# 02_-_CONNECTORS.net
KiCad netlist of a schematic drawn in Altium Designer
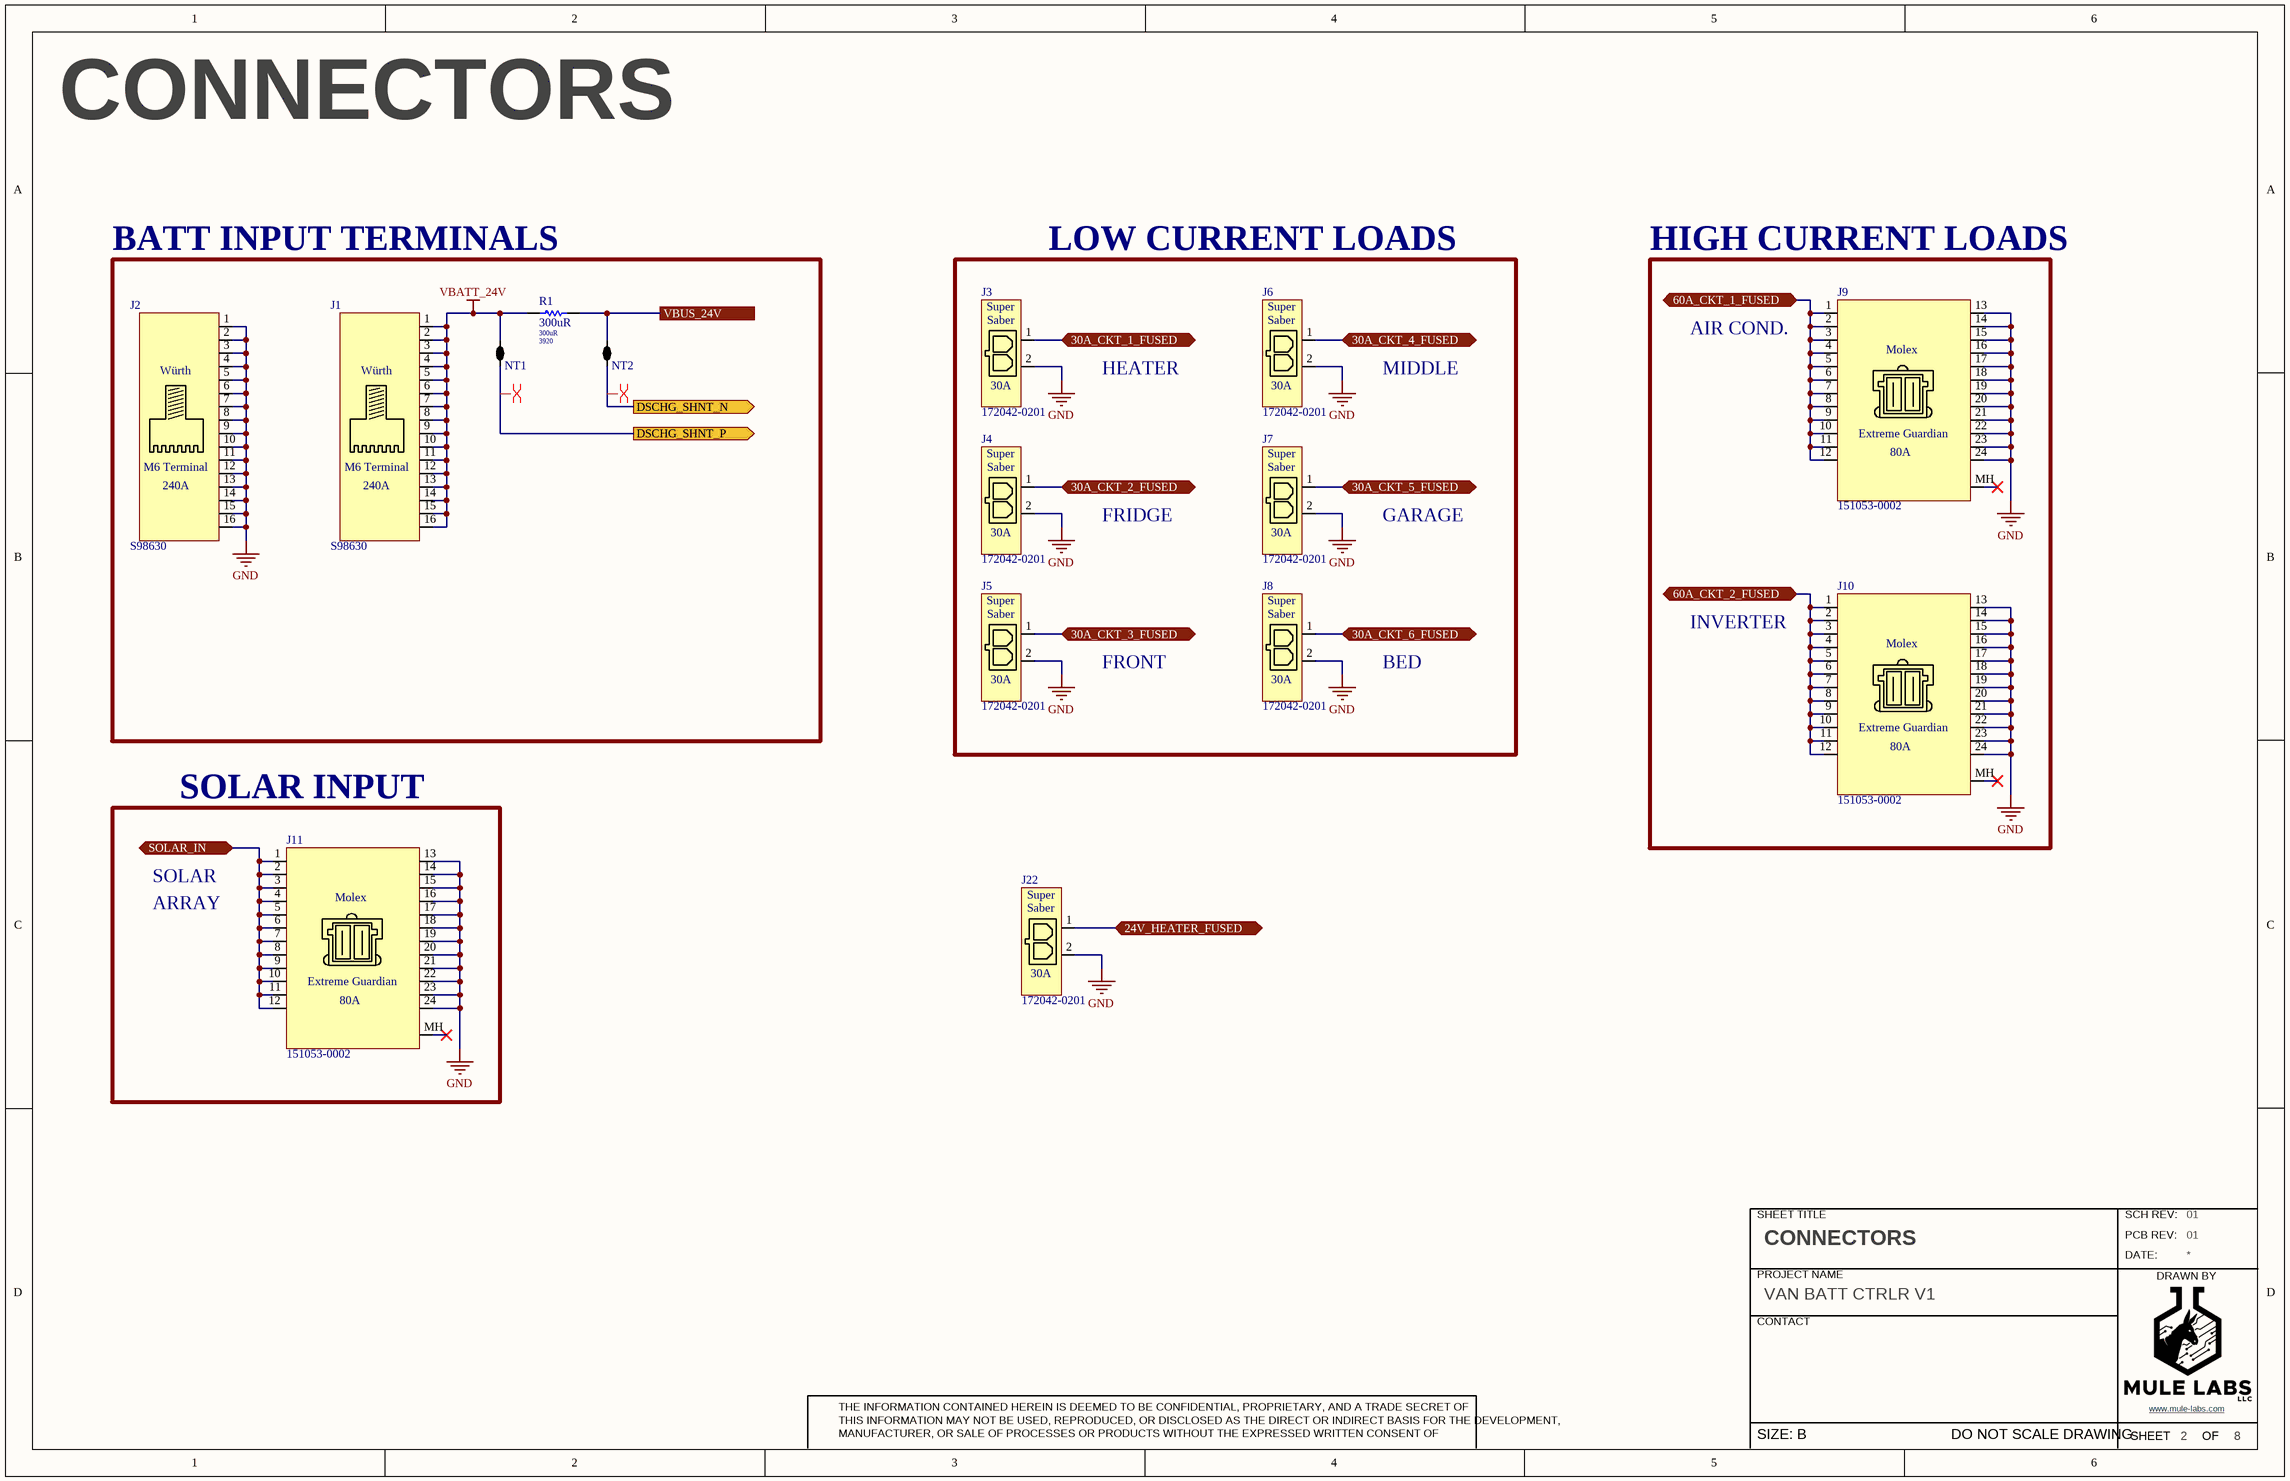
[diagram p0: [02] - CONNECTORS.SchDoc]

(export (version "E")
  (design (tool "Eeschema 10.0.6"))
  (components
    (comp (ref "J1")
      (value "S98630")
      (footprint "WURTH_S98630")
      (fields (field (name "MANUFACTURER") "Wurth Electronics"))
      (libsource (lib "Connectors") (part "S98630"))
    )
    (comp (ref "J2")
      (value "S98630")
      (footprint "WURTH_S98630")
      (fields (field (name "MANUFACTURER") "Wurth Electronics"))
      (libsource (lib "Connectors") (part "S98630"))
    )
    (comp (ref "J3")
      (value "172042-0201")
      (footprint "MOLEX_1720420201")
      (description "Conn Power HDR 2 POS 7.49mm Solder ST Thru-Hole 2 Terminal 1 Port Super Sabre™ Frame")
      (fields (field (name "MANUFACTURER") "Molex"))
      (libsource (lib "Connectors") (part "172042-0201"))
    )
    (comp (ref "J4")
      (value "172042-0201")
      (footprint "MOLEX_1720420201")
      (description "Conn Power HDR 2 POS 7.49mm Solder ST Thru-Hole 2 Terminal 1 Port Super Sabre™ Frame")
      (fields (field (name "MANUFACTURER") "Molex"))
      (libsource (lib "Connectors") (part "172042-0201"))
    )
    (comp (ref "J5")
      (value "172042-0201")
      (footprint "MOLEX_1720420201")
      (description "Conn Power HDR 2 POS 7.49mm Solder ST Thru-Hole 2 Terminal 1 Port Super Sabre™ Frame")
      (fields (field (name "MANUFACTURER") "Molex"))
      (libsource (lib "Connectors") (part "172042-0201"))
    )
    (comp (ref "J6")
      (value "172042-0201")
      (footprint "MOLEX_1720420201")
      (description "Conn Power HDR 2 POS 7.49mm Solder ST Thru-Hole 2 Terminal 1 Port Super Sabre™ Frame")
      (fields (field (name "MANUFACTURER") "Molex"))
      (libsource (lib "Connectors") (part "172042-0201"))
    )
    (comp (ref "J7")
      (value "172042-0201")
      (footprint "MOLEX_1720420201")
      (description "Conn Power HDR 2 POS 7.49mm Solder ST Thru-Hole 2 Terminal 1 Port Super Sabre™ Frame")
      (fields (field (name "MANUFACTURER") "Molex"))
      (libsource (lib "Connectors") (part "172042-0201"))
    )
    (comp (ref "J8")
      (value "172042-0201")
      (footprint "MOLEX_1720420201")
      (description "Conn Power HDR 2 POS 7.49mm Solder ST Thru-Hole 2 Terminal 1 Port Super Sabre™ Frame")
      (fields (field (name "MANUFACTURER") "Molex"))
      (libsource (lib "Connectors") (part "172042-0201"))
    )
    (comp (ref "J9")
      (value "151053-0002")
      (footprint "MOLEX_151053-0002")
      (fields (field (name "MANUFACTURER") "Molex"))
      (libsource (lib "Connectors") (part "151053-0002"))
    )
    (comp (ref "J10")
      (value "151053-0002")
      (footprint "MOLEX_151053-0002")
      (fields (field (name "MANUFACTURER") "Molex"))
      (libsource (lib "Connectors") (part "151053-0002"))
    )
    (comp (ref "J11")
      (value "151053-0002")
      (footprint "MOLEX_151053-0002")
      (fields (field (name "MANUFACTURER") "Molex"))
      (libsource (lib "Connectors") (part "151053-0002"))
    )
    (comp (ref "J22")
      (value "172042-0201")
      (footprint "MOLEX_1720420201")
      (description "Conn Power HDR 2 POS 7.49mm Solder ST Thru-Hole 2 Terminal 1 Port Super Sabre™ Frame")
      (fields (field (name "MANUFACTURER") "Molex"))
      (libsource (lib "Connectors") (part "172042-0201"))
    )
    (comp (ref "NT1")
      (value "2 way net tie junction")
      (footprint "2way_LP")
      (libsource (lib "Net Ties") (part "2way"))
    )
    (comp (ref "NT2")
      (value "2 way net tie junction")
      (footprint "2way_LP")
      (libsource (lib "Net Ties") (part "2way"))
    )
    (comp (ref "R1")
      (value "300uR")
      (footprint "VISHAY_3920")
      (description "CSM3920A 0R0030 1.0% S T 130800 Chip Resistor Strip 3920 (1052 Metric)")
      (fields
        (field (name "MANUFACTURER") "Vishay Precision Group")
        (field (name "MANUFACTURER PART NUMBER") "Y14840R00030F9R")
        (field (name "RESISTANCE") "300uR")
        (field (name "PACKAGE") "3920")
      )
      (libsource (lib "Resistors") (part "Y14840R00030F9R"))
    )
  )
  (nets
    (net (code "1") (name "/24V_HEATER_FUSED") (class "Default")
      (node (ref "J22") (pin "1") (pinfunction "1_1") (pintype "passive"))
    )
    (net (code "2") (name "/30A_CKT_1_FUSED") (class "Default")
      (node (ref "J3") (pin "1") (pinfunction "1_1") (pintype "passive"))
    )
    (net (code "3") (name "/30A_CKT_2_FUSED") (class "Default")
      (node (ref "J4") (pin "1") (pinfunction "1_1") (pintype "passive"))
    )
    (net (code "4") (name "/30A_CKT_3_FUSED") (class "Default")
      (node (ref "J5") (pin "1") (pinfunction "1_1") (pintype "passive"))
    )
    (net (code "5") (name "/30A_CKT_4_FUSED") (class "Default")
      (node (ref "J6") (pin "1") (pinfunction "1_1") (pintype "passive"))
    )
    (net (code "6") (name "/30A_CKT_5_FUSED") (class "Default")
      (node (ref "J7") (pin "1") (pinfunction "1_1") (pintype "passive"))
    )
    (net (code "7") (name "/30A_CKT_6_FUSED") (class "Default")
      (node (ref "J8") (pin "1") (pinfunction "1_1") (pintype "passive"))
    )
    (net (code "8") (name "/60A_CKT_1_FUSED") (class "Default")
      (node (ref "J9") (pin "1") (pinfunction "1_1") (pintype "passive"))
      (node (ref "J9") (pin "10") (pinfunction "10_10") (pintype "passive"))
      (node (ref "J9") (pin "11") (pinfunction "11_11") (pintype "passive"))
      (node (ref "J9") (pin "12") (pinfunction "12_12") (pintype "passive"))
      (node (ref "J9") (pin "2") (pinfunction "2_2") (pintype "passive"))
      (node (ref "J9") (pin "3") (pinfunction "3_3") (pintype "passive"))
      (node (ref "J9") (pin "4") (pinfunction "4_4") (pintype "passive"))
      (node (ref "J9") (pin "5") (pinfunction "5_5") (pintype "passive"))
      (node (ref "J9") (pin "6") (pinfunction "6_6") (pintype "passive"))
      (node (ref "J9") (pin "7") (pinfunction "7_7") (pintype "passive"))
      (node (ref "J9") (pin "8") (pinfunction "8_8") (pintype "passive"))
      (node (ref "J9") (pin "9") (pinfunction "9_9") (pintype "passive"))
    )
    (net (code "9") (name "/60A_CKT_2_FUSED") (class "Default")
      (node (ref "J10") (pin "1") (pinfunction "1_1") (pintype "passive"))
      (node (ref "J10") (pin "10") (pinfunction "10_10") (pintype "passive"))
      (node (ref "J10") (pin "11") (pinfunction "11_11") (pintype "passive"))
      (node (ref "J10") (pin "12") (pinfunction "12_12") (pintype "passive"))
      (node (ref "J10") (pin "2") (pinfunction "2_2") (pintype "passive"))
      (node (ref "J10") (pin "3") (pinfunction "3_3") (pintype "passive"))
      (node (ref "J10") (pin "4") (pinfunction "4_4") (pintype "passive"))
      (node (ref "J10") (pin "5") (pinfunction "5_5") (pintype "passive"))
      (node (ref "J10") (pin "6") (pinfunction "6_6") (pintype "passive"))
      (node (ref "J10") (pin "7") (pinfunction "7_7") (pintype "passive"))
      (node (ref "J10") (pin "8") (pinfunction "8_8") (pintype "passive"))
      (node (ref "J10") (pin "9") (pinfunction "9_9") (pintype "passive"))
    )
    (net (code "10") (name "/DSCHG_SHNT_N") (class "Default")
      (node (ref "NT2") (pin "1") (pinfunction "1_1") (pintype "passive"))
    )
    (net (code "11") (name "/DSCHG_SHNT_P") (class "Default")
      (node (ref "NT1") (pin "1") (pinfunction "1_1") (pintype "passive"))
    )
    (net (code "12") (name "/SOLAR_IN") (class "Default")
      (node (ref "J11") (pin "1") (pinfunction "1_1") (pintype "passive"))
      (node (ref "J11") (pin "10") (pinfunction "10_10") (pintype "passive"))
      (node (ref "J11") (pin "11") (pinfunction "11_11") (pintype "passive"))
      (node (ref "J11") (pin "12") (pinfunction "12_12") (pintype "passive"))
      (node (ref "J11") (pin "2") (pinfunction "2_2") (pintype "passive"))
      (node (ref "J11") (pin "3") (pinfunction "3_3") (pintype "passive"))
      (node (ref "J11") (pin "4") (pinfunction "4_4") (pintype "passive"))
      (node (ref "J11") (pin "5") (pinfunction "5_5") (pintype "passive"))
      (node (ref "J11") (pin "6") (pinfunction "6_6") (pintype "passive"))
      (node (ref "J11") (pin "7") (pinfunction "7_7") (pintype "passive"))
      (node (ref "J11") (pin "8") (pinfunction "8_8") (pintype "passive"))
      (node (ref "J11") (pin "9") (pinfunction "9_9") (pintype "passive"))
    )
    (net (code "13") (name "/VBUS_24V") (class "Default")
      (node (ref "NT2") (pin "2") (pinfunction "2_2") (pintype "passive"))
      (node (ref "R1") (pin "1") (pintype "passive"))
    )
    (net (code "14") (name "GND") (class "Default")
      (node (ref "J10") (pin "13") (pinfunction "13_13") (pintype "passive"))
      (node (ref "J10") (pin "14") (pinfunction "14_14") (pintype "passive"))
      (node (ref "J10") (pin "15") (pinfunction "15_15") (pintype "passive"))
      (node (ref "J10") (pin "16") (pinfunction "16_16") (pintype "passive"))
      (node (ref "J10") (pin "17") (pinfunction "17_17") (pintype "passive"))
      (node (ref "J10") (pin "18") (pinfunction "18_18") (pintype "passive"))
      (node (ref "J10") (pin "19") (pinfunction "19_19") (pintype "passive"))
      (node (ref "J10") (pin "20") (pinfunction "20_20") (pintype "passive"))
      (node (ref "J10") (pin "21") (pinfunction "21_21") (pintype "passive"))
      (node (ref "J10") (pin "22") (pinfunction "22_22") (pintype "passive"))
      (node (ref "J10") (pin "23") (pinfunction "23_23") (pintype "passive"))
      (node (ref "J10") (pin "24") (pinfunction "24_24") (pintype "passive"))
      (node (ref "J11") (pin "13") (pinfunction "13_13") (pintype "passive"))
      (node (ref "J11") (pin "14") (pinfunction "14_14") (pintype "passive"))
      (node (ref "J11") (pin "15") (pinfunction "15_15") (pintype "passive"))
      (node (ref "J11") (pin "16") (pinfunction "16_16") (pintype "passive"))
      (node (ref "J11") (pin "17") (pinfunction "17_17") (pintype "passive"))
      (node (ref "J11") (pin "18") (pinfunction "18_18") (pintype "passive"))
      (node (ref "J11") (pin "19") (pinfunction "19_19") (pintype "passive"))
      (node (ref "J11") (pin "20") (pinfunction "20_20") (pintype "passive"))
      (node (ref "J11") (pin "21") (pinfunction "21_21") (pintype "passive"))
      (node (ref "J11") (pin "22") (pinfunction "22_22") (pintype "passive"))
      (node (ref "J11") (pin "23") (pinfunction "23_23") (pintype "passive"))
      (node (ref "J11") (pin "24") (pinfunction "24_24") (pintype "passive"))
      (node (ref "J2") (pin "1") (pinfunction "1_1") (pintype "passive"))
      (node (ref "J2") (pin "10") (pinfunction "10_10") (pintype "passive"))
      (node (ref "J2") (pin "11") (pinfunction "11_11") (pintype "passive"))
      (node (ref "J2") (pin "12") (pinfunction "12_12") (pintype "passive"))
      (node (ref "J2") (pin "13") (pinfunction "13_13") (pintype "passive"))
      (node (ref "J2") (pin "14") (pinfunction "14_14") (pintype "passive"))
      (node (ref "J2") (pin "15") (pinfunction "15_15") (pintype "passive"))
      (node (ref "J2") (pin "16") (pinfunction "16_16") (pintype "passive"))
      (node (ref "J2") (pin "2") (pinfunction "2_2") (pintype "passive"))
      (node (ref "J2") (pin "3") (pinfunction "3_3") (pintype "passive"))
      (node (ref "J2") (pin "4") (pinfunction "4_4") (pintype "passive"))
      (node (ref "J2") (pin "5") (pinfunction "5_5") (pintype "passive"))
      (node (ref "J2") (pin "6") (pinfunction "6_6") (pintype "passive"))
      (node (ref "J2") (pin "7") (pinfunction "7_7") (pintype "passive"))
      (node (ref "J2") (pin "8") (pinfunction "8_8") (pintype "passive"))
      (node (ref "J2") (pin "9") (pinfunction "9_9") (pintype "passive"))
      (node (ref "J22") (pin "2") (pinfunction "2_2") (pintype "passive"))
      (node (ref "J3") (pin "2") (pinfunction "2_2") (pintype "passive"))
      (node (ref "J4") (pin "2") (pinfunction "2_2") (pintype "passive"))
      (node (ref "J5") (pin "2") (pinfunction "2_2") (pintype "passive"))
      (node (ref "J6") (pin "2") (pinfunction "2_2") (pintype "passive"))
      (node (ref "J7") (pin "2") (pinfunction "2_2") (pintype "passive"))
      (node (ref "J8") (pin "2") (pinfunction "2_2") (pintype "passive"))
      (node (ref "J9") (pin "13") (pinfunction "13_13") (pintype "passive"))
      (node (ref "J9") (pin "14") (pinfunction "14_14") (pintype "passive"))
      (node (ref "J9") (pin "15") (pinfunction "15_15") (pintype "passive"))
      (node (ref "J9") (pin "16") (pinfunction "16_16") (pintype "passive"))
      (node (ref "J9") (pin "17") (pinfunction "17_17") (pintype "passive"))
      (node (ref "J9") (pin "18") (pinfunction "18_18") (pintype "passive"))
      (node (ref "J9") (pin "19") (pinfunction "19_19") (pintype "passive"))
      (node (ref "J9") (pin "20") (pinfunction "20_20") (pintype "passive"))
      (node (ref "J9") (pin "21") (pinfunction "21_21") (pintype "passive"))
      (node (ref "J9") (pin "22") (pinfunction "22_22") (pintype "passive"))
      (node (ref "J9") (pin "23") (pinfunction "23_23") (pintype "passive"))
      (node (ref "J9") (pin "24") (pinfunction "24_24") (pintype "passive"))
    )
    (net (code "15") (name "VBATT_24V") (class "Default")
      (node (ref "J1") (pin "1") (pinfunction "1_1") (pintype "passive"))
      (node (ref "J1") (pin "10") (pinfunction "10_10") (pintype "passive"))
      (node (ref "J1") (pin "11") (pinfunction "11_11") (pintype "passive"))
      (node (ref "J1") (pin "12") (pinfunction "12_12") (pintype "passive"))
      (node (ref "J1") (pin "13") (pinfunction "13_13") (pintype "passive"))
      (node (ref "J1") (pin "14") (pinfunction "14_14") (pintype "passive"))
      (node (ref "J1") (pin "15") (pinfunction "15_15") (pintype "passive"))
      (node (ref "J1") (pin "16") (pinfunction "16_16") (pintype "passive"))
      (node (ref "J1") (pin "2") (pinfunction "2_2") (pintype "passive"))
      (node (ref "J1") (pin "3") (pinfunction "3_3") (pintype "passive"))
      (node (ref "J1") (pin "4") (pinfunction "4_4") (pintype "passive"))
      (node (ref "J1") (pin "5") (pinfunction "5_5") (pintype "passive"))
      (node (ref "J1") (pin "6") (pinfunction "6_6") (pintype "passive"))
      (node (ref "J1") (pin "7") (pinfunction "7_7") (pintype "passive"))
      (node (ref "J1") (pin "8") (pinfunction "8_8") (pintype "passive"))
      (node (ref "J1") (pin "9") (pinfunction "9_9") (pintype "passive"))
      (node (ref "NT1") (pin "2") (pinfunction "2_2") (pintype "passive"))
      (node (ref "R1") (pin "2") (pintype "passive"))
    )
    (net (code "16") (name "unconnected-(J9-22-PadMH)") (class "Default")
      (node (ref "J9") (pin "MH") (pinfunction "22_MH") (pintype "passive+no_connect"))
    )
    (net (code "17") (name "unconnected-(J10-22-PadMH)") (class "Default")
      (node (ref "J10") (pin "MH") (pinfunction "22_MH") (pintype "passive+no_connect"))
    )
    (net (code "18") (name "unconnected-(J11-22-PadMH)") (class "Default")
      (node (ref "J11") (pin "MH") (pinfunction "22_MH") (pintype "passive+no_connect"))
    )
  )
)
